# led28.net
KiCad netlist of a schematic drawn in EAGLE
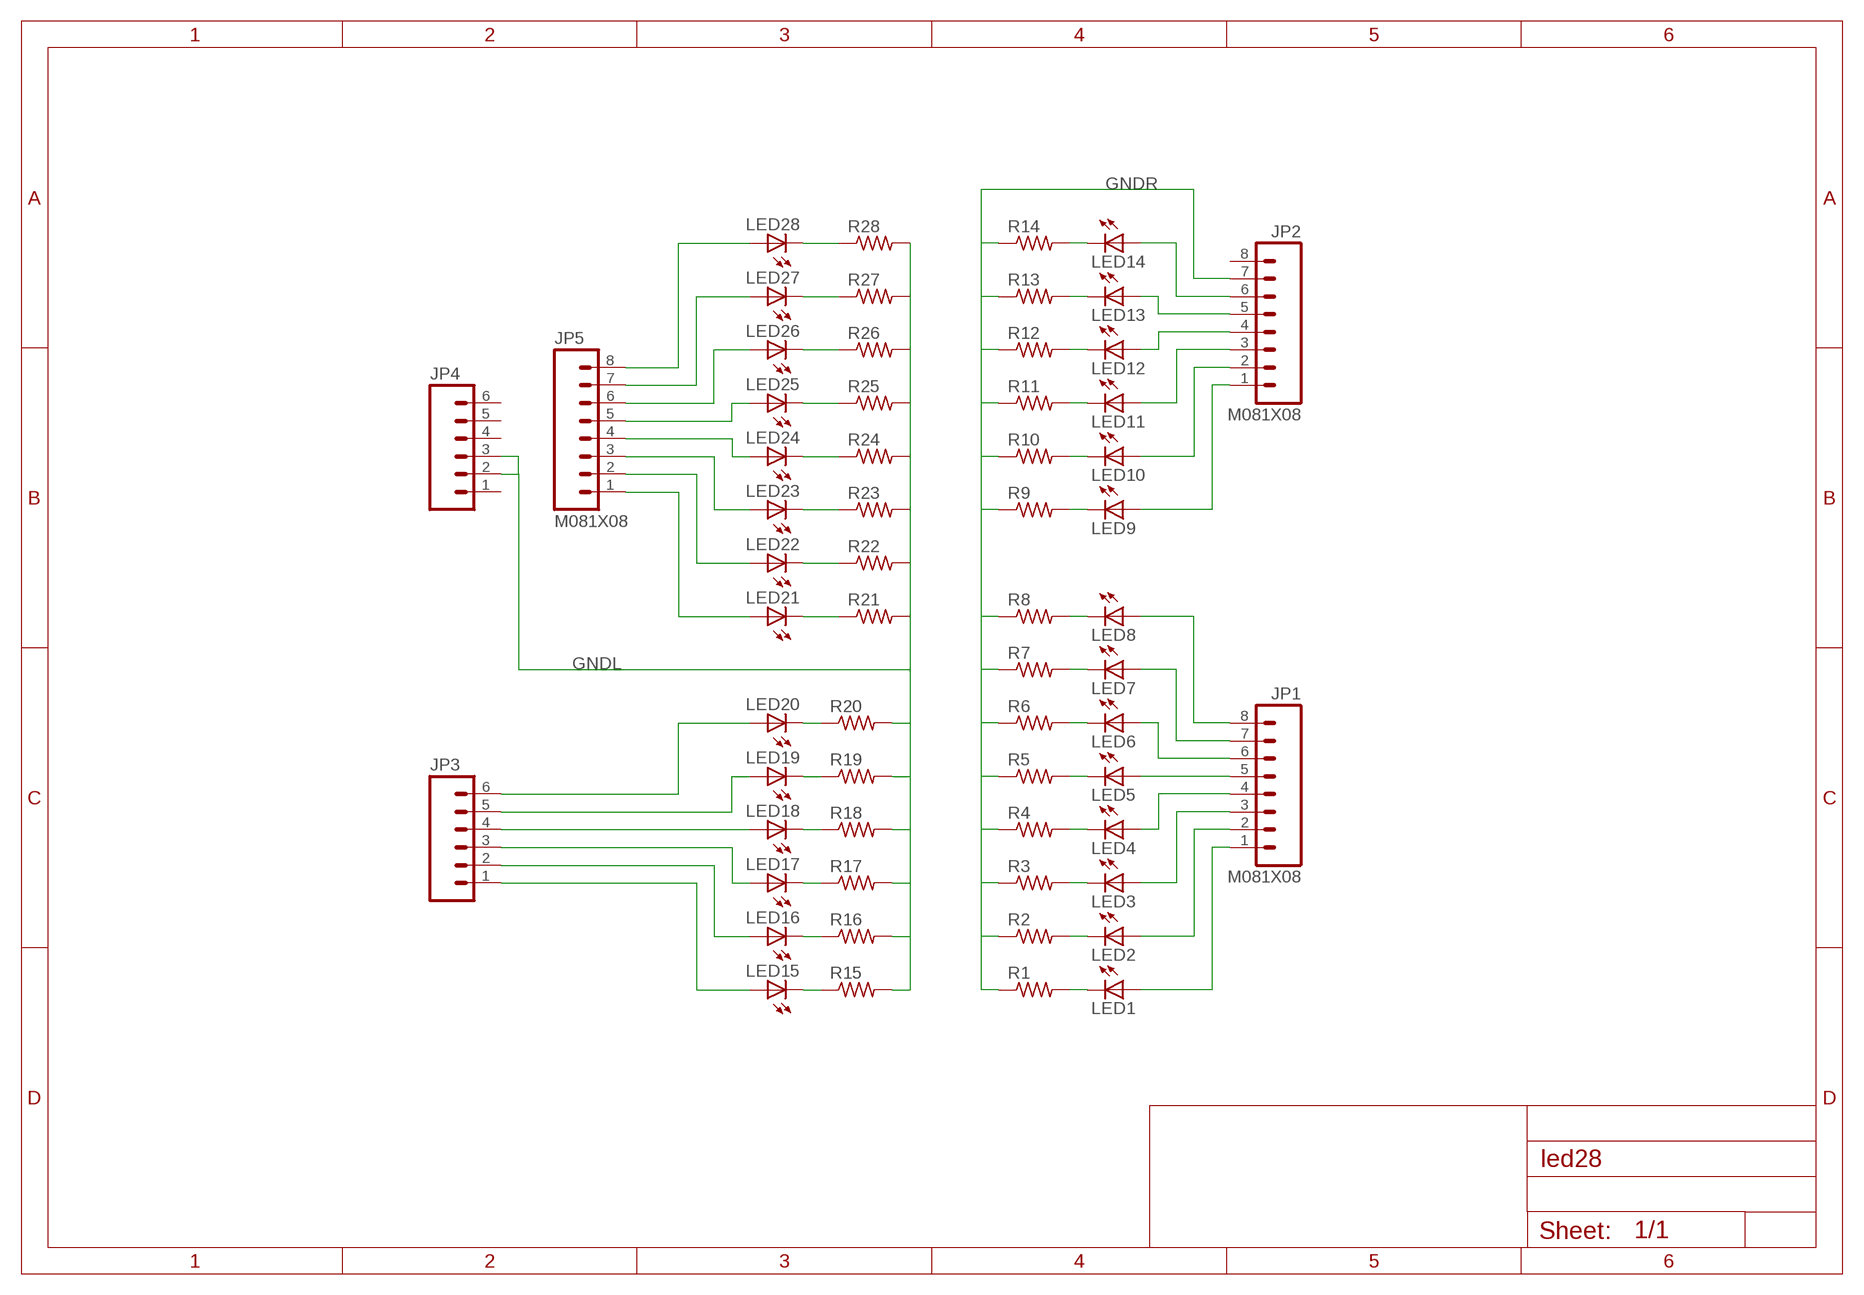
[diagram p0: schematic, sheet 1]

(export (version "E")
  (design (tool "Eeschema 10.0.6"))
  (components
    (comp (ref "JP1")
      (value "M081X08")
      (footprint "eagle-import:1X08_NARROW")
      (libsource (lib "eagle-import") (part "M081X08"))
    )
    (comp (ref "JP2")
      (value "M081X08")
      (footprint "eagle-import:1X08_NARROW")
      (libsource (lib "eagle-import") (part "M081X08"))
    )
    (comp (ref "JP3")
      (value "M06SIP")
      (footprint "eagle-import:1X06_NARROW")
      (libsource (lib "eagle-import") (part "M06SIP"))
    )
    (comp (ref "JP4")
      (value "M06SIP")
      (footprint "eagle-import:1X06_NARROW")
      (libsource (lib "eagle-import") (part "M06SIP"))
    )
    (comp (ref "JP5")
      (value "M081X08")
      (footprint "eagle-import:1X08_NARROW")
      (libsource (lib "eagle-import") (part "M081X08"))
    )
    (comp (ref "LED1")
      (value "LEDCHIP-LED0603")
      (footprint "eagle-import:CHIP-LED0603")
      (libsource (lib "eagle-import") (part "LEDCHIP-LED0603"))
    )
    (comp (ref "LED2")
      (value "LEDCHIP-LED0603")
      (footprint "eagle-import:CHIP-LED0603")
      (libsource (lib "eagle-import") (part "LEDCHIP-LED0603"))
    )
    (comp (ref "LED3")
      (value "LEDCHIP-LED0603")
      (footprint "eagle-import:CHIP-LED0603")
      (libsource (lib "eagle-import") (part "LEDCHIP-LED0603"))
    )
    (comp (ref "LED4")
      (value "LEDCHIP-LED0603")
      (footprint "eagle-import:CHIP-LED0603")
      (libsource (lib "eagle-import") (part "LEDCHIP-LED0603"))
    )
    (comp (ref "LED5")
      (value "LEDCHIP-LED0603")
      (footprint "eagle-import:CHIP-LED0603")
      (libsource (lib "eagle-import") (part "LEDCHIP-LED0603"))
    )
    (comp (ref "LED6")
      (value "LEDCHIP-LED0603")
      (footprint "eagle-import:CHIP-LED0603")
      (libsource (lib "eagle-import") (part "LEDCHIP-LED0603"))
    )
    (comp (ref "LED7")
      (value "LEDCHIP-LED0603")
      (footprint "eagle-import:CHIP-LED0603")
      (libsource (lib "eagle-import") (part "LEDCHIP-LED0603"))
    )
    (comp (ref "LED8")
      (value "LEDCHIP-LED0603")
      (footprint "eagle-import:CHIP-LED0603")
      (libsource (lib "eagle-import") (part "LEDCHIP-LED0603"))
    )
    (comp (ref "LED9")
      (value "LEDCHIP-LED0603")
      (footprint "eagle-import:CHIP-LED0603")
      (libsource (lib "eagle-import") (part "LEDCHIP-LED0603"))
    )
    (comp (ref "LED10")
      (value "LEDCHIP-LED0603")
      (footprint "eagle-import:CHIP-LED0603")
      (libsource (lib "eagle-import") (part "LEDCHIP-LED0603"))
    )
    (comp (ref "LED11")
      (value "LEDCHIP-LED0603")
      (footprint "eagle-import:CHIP-LED0603")
      (libsource (lib "eagle-import") (part "LEDCHIP-LED0603"))
    )
    (comp (ref "LED12")
      (value "LEDCHIP-LED0603")
      (footprint "eagle-import:CHIP-LED0603")
      (libsource (lib "eagle-import") (part "LEDCHIP-LED0603"))
    )
    (comp (ref "LED13")
      (value "LEDCHIP-LED0603")
      (footprint "eagle-import:CHIP-LED0603")
      (libsource (lib "eagle-import") (part "LEDCHIP-LED0603"))
    )
    (comp (ref "LED14")
      (value "LEDCHIP-LED0603")
      (footprint "eagle-import:CHIP-LED0603")
      (libsource (lib "eagle-import") (part "LEDCHIP-LED0603"))
    )
    (comp (ref "LED15")
      (value "LEDCHIP-LED0603")
      (footprint "eagle-import:CHIP-LED0603")
      (libsource (lib "eagle-import") (part "LEDCHIP-LED0603"))
    )
    (comp (ref "LED16")
      (value "LEDCHIP-LED0603")
      (footprint "eagle-import:CHIP-LED0603")
      (libsource (lib "eagle-import") (part "LEDCHIP-LED0603"))
    )
    (comp (ref "LED17")
      (value "LEDCHIP-LED0603")
      (footprint "eagle-import:CHIP-LED0603")
      (libsource (lib "eagle-import") (part "LEDCHIP-LED0603"))
    )
    (comp (ref "LED18")
      (value "LEDCHIP-LED0603")
      (footprint "eagle-import:CHIP-LED0603")
      (libsource (lib "eagle-import") (part "LEDCHIP-LED0603"))
    )
    (comp (ref "LED19")
      (value "LEDCHIP-LED0603")
      (footprint "eagle-import:CHIP-LED0603")
      (libsource (lib "eagle-import") (part "LEDCHIP-LED0603"))
    )
    (comp (ref "LED20")
      (value "LEDCHIP-LED0603")
      (footprint "eagle-import:CHIP-LED0603")
      (libsource (lib "eagle-import") (part "LEDCHIP-LED0603"))
    )
    (comp (ref "LED21")
      (value "LEDCHIP-LED0603")
      (footprint "eagle-import:CHIP-LED0603")
      (libsource (lib "eagle-import") (part "LEDCHIP-LED0603"))
    )
    (comp (ref "LED22")
      (value "LEDCHIP-LED0603")
      (footprint "eagle-import:CHIP-LED0603")
      (libsource (lib "eagle-import") (part "LEDCHIP-LED0603"))
    )
    (comp (ref "LED23")
      (value "LEDCHIP-LED0603")
      (footprint "eagle-import:CHIP-LED0603")
      (libsource (lib "eagle-import") (part "LEDCHIP-LED0603"))
    )
    (comp (ref "LED24")
      (value "LEDCHIP-LED0603")
      (footprint "eagle-import:CHIP-LED0603")
      (libsource (lib "eagle-import") (part "LEDCHIP-LED0603"))
    )
    (comp (ref "LED25")
      (value "LEDCHIP-LED0603")
      (footprint "eagle-import:CHIP-LED0603")
      (libsource (lib "eagle-import") (part "LEDCHIP-LED0603"))
    )
    (comp (ref "LED26")
      (value "LEDCHIP-LED0603")
      (footprint "eagle-import:CHIP-LED0603")
      (libsource (lib "eagle-import") (part "LEDCHIP-LED0603"))
    )
    (comp (ref "LED27")
      (value "LEDCHIP-LED0603")
      (footprint "eagle-import:CHIP-LED0603")
      (libsource (lib "eagle-import") (part "LEDCHIP-LED0603"))
    )
    (comp (ref "LED28")
      (value "LEDCHIP-LED0603")
      (footprint "eagle-import:CHIP-LED0603")
      (libsource (lib "eagle-import") (part "LEDCHIP-LED0603"))
    )
    (comp (ref "R1")
      (value "R-US_R0603")
      (footprint "eagle-import:R0603")
      (libsource (lib "eagle-import") (part "R-US_R0603"))
    )
    (comp (ref "R2")
      (value "R-US_R0603")
      (footprint "eagle-import:R0603")
      (libsource (lib "eagle-import") (part "R-US_R0603"))
    )
    (comp (ref "R3")
      (value "R-US_R0603")
      (footprint "eagle-import:R0603")
      (libsource (lib "eagle-import") (part "R-US_R0603"))
    )
    (comp (ref "R4")
      (value "R-US_R0603")
      (footprint "eagle-import:R0603")
      (libsource (lib "eagle-import") (part "R-US_R0603"))
    )
    (comp (ref "R5")
      (value "R-US_R0603")
      (footprint "eagle-import:R0603")
      (libsource (lib "eagle-import") (part "R-US_R0603"))
    )
    (comp (ref "R6")
      (value "R-US_R0603")
      (footprint "eagle-import:R0603")
      (libsource (lib "eagle-import") (part "R-US_R0603"))
    )
    (comp (ref "R7")
      (value "R-US_R0603")
      (footprint "eagle-import:R0603")
      (libsource (lib "eagle-import") (part "R-US_R0603"))
    )
    (comp (ref "R8")
      (value "R-US_R0603")
      (footprint "eagle-import:R0603")
      (libsource (lib "eagle-import") (part "R-US_R0603"))
    )
    (comp (ref "R9")
      (value "R-US_R0603")
      (footprint "eagle-import:R0603")
      (libsource (lib "eagle-import") (part "R-US_R0603"))
    )
    (comp (ref "R10")
      (value "R-US_R0603")
      (footprint "eagle-import:R0603")
      (libsource (lib "eagle-import") (part "R-US_R0603"))
    )
    (comp (ref "R11")
      (value "R-US_R0603")
      (footprint "eagle-import:R0603")
      (libsource (lib "eagle-import") (part "R-US_R0603"))
    )
    (comp (ref "R12")
      (value "R-US_R0603")
      (footprint "eagle-import:R0603")
      (libsource (lib "eagle-import") (part "R-US_R0603"))
    )
    (comp (ref "R13")
      (value "R-US_R0603")
      (footprint "eagle-import:R0603")
      (libsource (lib "eagle-import") (part "R-US_R0603"))
    )
    (comp (ref "R14")
      (value "R-US_R0603")
      (footprint "eagle-import:R0603")
      (libsource (lib "eagle-import") (part "R-US_R0603"))
    )
    (comp (ref "R15")
      (value "R-US_R0603")
      (footprint "eagle-import:R0603")
      (libsource (lib "eagle-import") (part "R-US_R0603"))
    )
    (comp (ref "R16")
      (value "R-US_R0603")
      (footprint "eagle-import:R0603")
      (libsource (lib "eagle-import") (part "R-US_R0603"))
    )
    (comp (ref "R17")
      (value "R-US_R0603")
      (footprint "eagle-import:R0603")
      (libsource (lib "eagle-import") (part "R-US_R0603"))
    )
    (comp (ref "R18")
      (value "R-US_R0603")
      (footprint "eagle-import:R0603")
      (libsource (lib "eagle-import") (part "R-US_R0603"))
    )
    (comp (ref "R19")
      (value "R-US_R0603")
      (footprint "eagle-import:R0603")
      (libsource (lib "eagle-import") (part "R-US_R0603"))
    )
    (comp (ref "R20")
      (value "R-US_R0603")
      (footprint "eagle-import:R0603")
      (libsource (lib "eagle-import") (part "R-US_R0603"))
    )
    (comp (ref "R21")
      (value "R-US_R0603")
      (footprint "eagle-import:R0603")
      (libsource (lib "eagle-import") (part "R-US_R0603"))
    )
    (comp (ref "R22")
      (value "R-US_R0603")
      (footprint "eagle-import:R0603")
      (libsource (lib "eagle-import") (part "R-US_R0603"))
    )
    (comp (ref "R23")
      (value "R-US_R0603")
      (footprint "eagle-import:R0603")
      (libsource (lib "eagle-import") (part "R-US_R0603"))
    )
    (comp (ref "R24")
      (value "R-US_R0603")
      (footprint "eagle-import:R0603")
      (libsource (lib "eagle-import") (part "R-US_R0603"))
    )
    (comp (ref "R25")
      (value "R-US_R0603")
      (footprint "eagle-import:R0603")
      (libsource (lib "eagle-import") (part "R-US_R0603"))
    )
    (comp (ref "R26")
      (value "R-US_R0603")
      (footprint "eagle-import:R0603")
      (libsource (lib "eagle-import") (part "R-US_R0603"))
    )
    (comp (ref "R27")
      (value "R-US_R0603")
      (footprint "eagle-import:R0603")
      (libsource (lib "eagle-import") (part "R-US_R0603"))
    )
    (comp (ref "R28")
      (value "R-US_R0603")
      (footprint "eagle-import:R0603")
      (libsource (lib "eagle-import") (part "R-US_R0603"))
    )
  )
  (nets
    (net (code "1") (name "/GNDL") (class "Default")
      (node (ref "JP4") (pin "2") (pinfunction "2_2") (pintype "passive"))
      (node (ref "JP4") (pin "3") (pinfunction "3_3") (pintype "passive"))
      (node (ref "R15") (pin "2") (pinfunction "2_2") (pintype "passive"))
      (node (ref "R16") (pin "2") (pinfunction "2_2") (pintype "passive"))
      (node (ref "R17") (pin "2") (pinfunction "2_2") (pintype "passive"))
      (node (ref "R18") (pin "2") (pinfunction "2_2") (pintype "passive"))
      (node (ref "R19") (pin "2") (pinfunction "2_2") (pintype "passive"))
      (node (ref "R20") (pin "2") (pinfunction "2_2") (pintype "passive"))
      (node (ref "R21") (pin "2") (pinfunction "2_2") (pintype "passive"))
      (node (ref "R22") (pin "2") (pinfunction "2_2") (pintype "passive"))
      (node (ref "R23") (pin "2") (pinfunction "2_2") (pintype "passive"))
      (node (ref "R24") (pin "2") (pinfunction "2_2") (pintype "passive"))
      (node (ref "R25") (pin "2") (pinfunction "2_2") (pintype "passive"))
      (node (ref "R26") (pin "2") (pinfunction "2_2") (pintype "passive"))
      (node (ref "R27") (pin "2") (pinfunction "2_2") (pintype "passive"))
      (node (ref "R28") (pin "2") (pinfunction "2_2") (pintype "passive"))
    )
    (net (code "2") (name "/GNDR") (class "Default")
      (node (ref "JP2") (pin "7") (pinfunction "7_7") (pintype "passive"))
      (node (ref "R1") (pin "1") (pinfunction "1_1") (pintype "passive"))
      (node (ref "R10") (pin "1") (pinfunction "1_1") (pintype "passive"))
      (node (ref "R11") (pin "1") (pinfunction "1_1") (pintype "passive"))
      (node (ref "R12") (pin "1") (pinfunction "1_1") (pintype "passive"))
      (node (ref "R13") (pin "1") (pinfunction "1_1") (pintype "passive"))
      (node (ref "R14") (pin "1") (pinfunction "1_1") (pintype "passive"))
      (node (ref "R2") (pin "1") (pinfunction "1_1") (pintype "passive"))
      (node (ref "R3") (pin "1") (pinfunction "1_1") (pintype "passive"))
      (node (ref "R4") (pin "1") (pinfunction "1_1") (pintype "passive"))
      (node (ref "R5") (pin "1") (pinfunction "1_1") (pintype "passive"))
      (node (ref "R6") (pin "1") (pinfunction "1_1") (pintype "passive"))
      (node (ref "R7") (pin "1") (pinfunction "1_1") (pintype "passive"))
      (node (ref "R8") (pin "1") (pinfunction "1_1") (pintype "passive"))
      (node (ref "R9") (pin "1") (pinfunction "1_1") (pintype "passive"))
    )
    (net (code "3") (name "Net-(JP1-Pad1)") (class "Default")
      (node (ref "JP1") (pin "1") (pinfunction "1_1") (pintype "passive"))
      (node (ref "LED1") (pin "A") (pinfunction "A_A") (pintype "passive"))
    )
    (net (code "4") (name "Net-(JP1-Pad2)") (class "Default")
      (node (ref "JP1") (pin "2") (pinfunction "2_2") (pintype "passive"))
      (node (ref "LED2") (pin "A") (pinfunction "A_A") (pintype "passive"))
    )
    (net (code "5") (name "Net-(JP1-Pad3)") (class "Default")
      (node (ref "JP1") (pin "3") (pinfunction "3_3") (pintype "passive"))
      (node (ref "LED3") (pin "A") (pinfunction "A_A") (pintype "passive"))
    )
    (net (code "6") (name "Net-(JP1-Pad4)") (class "Default")
      (node (ref "JP1") (pin "4") (pinfunction "4_4") (pintype "passive"))
      (node (ref "LED4") (pin "A") (pinfunction "A_A") (pintype "passive"))
    )
    (net (code "7") (name "Net-(JP1-Pad5)") (class "Default")
      (node (ref "JP1") (pin "5") (pinfunction "5_5") (pintype "passive"))
      (node (ref "LED5") (pin "A") (pinfunction "A_A") (pintype "passive"))
    )
    (net (code "8") (name "Net-(JP1-Pad6)") (class "Default")
      (node (ref "JP1") (pin "6") (pinfunction "6_6") (pintype "passive"))
      (node (ref "LED6") (pin "A") (pinfunction "A_A") (pintype "passive"))
    )
    (net (code "9") (name "Net-(JP1-Pad7)") (class "Default")
      (node (ref "JP1") (pin "7") (pinfunction "7_7") (pintype "passive"))
      (node (ref "LED7") (pin "A") (pinfunction "A_A") (pintype "passive"))
    )
    (net (code "10") (name "Net-(JP1-Pad8)") (class "Default")
      (node (ref "JP1") (pin "8") (pinfunction "8_8") (pintype "passive"))
      (node (ref "LED8") (pin "A") (pinfunction "A_A") (pintype "passive"))
    )
    (net (code "11") (name "Net-(JP2-Pad1)") (class "Default")
      (node (ref "JP2") (pin "1") (pinfunction "1_1") (pintype "passive"))
      (node (ref "LED9") (pin "A") (pinfunction "A_A") (pintype "passive"))
    )
    (net (code "12") (name "Net-(JP2-Pad2)") (class "Default")
      (node (ref "JP2") (pin "2") (pinfunction "2_2") (pintype "passive"))
      (node (ref "LED10") (pin "A") (pinfunction "A_A") (pintype "passive"))
    )
    (net (code "13") (name "Net-(JP2-Pad3)") (class "Default")
      (node (ref "JP2") (pin "3") (pinfunction "3_3") (pintype "passive"))
      (node (ref "LED11") (pin "A") (pinfunction "A_A") (pintype "passive"))
    )
    (net (code "14") (name "Net-(JP2-Pad4)") (class "Default")
      (node (ref "JP2") (pin "4") (pinfunction "4_4") (pintype "passive"))
      (node (ref "LED12") (pin "A") (pinfunction "A_A") (pintype "passive"))
    )
    (net (code "15") (name "Net-(JP2-Pad5)") (class "Default")
      (node (ref "JP2") (pin "5") (pinfunction "5_5") (pintype "passive"))
      (node (ref "LED13") (pin "A") (pinfunction "A_A") (pintype "passive"))
    )
    (net (code "16") (name "Net-(JP2-Pad6)") (class "Default")
      (node (ref "JP2") (pin "6") (pinfunction "6_6") (pintype "passive"))
      (node (ref "LED14") (pin "A") (pinfunction "A_A") (pintype "passive"))
    )
    (net (code "17") (name "Net-(JP3-Pad1)") (class "Default")
      (node (ref "JP3") (pin "1") (pinfunction "1_1") (pintype "passive"))
      (node (ref "LED15") (pin "A") (pinfunction "A_A") (pintype "passive"))
    )
    (net (code "18") (name "Net-(JP3-Pad2)") (class "Default")
      (node (ref "JP3") (pin "2") (pinfunction "2_2") (pintype "passive"))
      (node (ref "LED16") (pin "A") (pinfunction "A_A") (pintype "passive"))
    )
    (net (code "19") (name "Net-(JP3-Pad3)") (class "Default")
      (node (ref "JP3") (pin "3") (pinfunction "3_3") (pintype "passive"))
      (node (ref "LED17") (pin "A") (pinfunction "A_A") (pintype "passive"))
    )
    (net (code "20") (name "Net-(JP3-Pad4)") (class "Default")
      (node (ref "JP3") (pin "4") (pinfunction "4_4") (pintype "passive"))
      (node (ref "LED18") (pin "A") (pinfunction "A_A") (pintype "passive"))
    )
    (net (code "21") (name "Net-(JP3-Pad5)") (class "Default")
      (node (ref "JP3") (pin "5") (pinfunction "5_5") (pintype "passive"))
      (node (ref "LED19") (pin "A") (pinfunction "A_A") (pintype "passive"))
    )
    (net (code "22") (name "Net-(JP3-Pad6)") (class "Default")
      (node (ref "JP3") (pin "6") (pinfunction "6_6") (pintype "passive"))
      (node (ref "LED20") (pin "A") (pinfunction "A_A") (pintype "passive"))
    )
    (net (code "23") (name "Net-(JP5-Pad1)") (class "Default")
      (node (ref "JP5") (pin "1") (pinfunction "1_1") (pintype "passive"))
      (node (ref "LED21") (pin "A") (pinfunction "A_A") (pintype "passive"))
    )
    (net (code "24") (name "Net-(JP5-Pad2)") (class "Default")
      (node (ref "JP5") (pin "2") (pinfunction "2_2") (pintype "passive"))
      (node (ref "LED22") (pin "A") (pinfunction "A_A") (pintype "passive"))
    )
    (net (code "25") (name "Net-(JP5-Pad3)") (class "Default")
      (node (ref "JP5") (pin "3") (pinfunction "3_3") (pintype "passive"))
      (node (ref "LED23") (pin "A") (pinfunction "A_A") (pintype "passive"))
    )
    (net (code "26") (name "Net-(JP5-Pad4)") (class "Default")
      (node (ref "JP5") (pin "4") (pinfunction "4_4") (pintype "passive"))
      (node (ref "LED24") (pin "A") (pinfunction "A_A") (pintype "passive"))
    )
    (net (code "27") (name "Net-(JP5-Pad5)") (class "Default")
      (node (ref "JP5") (pin "5") (pinfunction "5_5") (pintype "passive"))
      (node (ref "LED25") (pin "A") (pinfunction "A_A") (pintype "passive"))
    )
    (net (code "28") (name "Net-(JP5-Pad6)") (class "Default")
      (node (ref "JP5") (pin "6") (pinfunction "6_6") (pintype "passive"))
      (node (ref "LED26") (pin "A") (pinfunction "A_A") (pintype "passive"))
    )
    (net (code "29") (name "Net-(JP5-Pad7)") (class "Default")
      (node (ref "JP5") (pin "7") (pinfunction "7_7") (pintype "passive"))
      (node (ref "LED27") (pin "A") (pinfunction "A_A") (pintype "passive"))
    )
    (net (code "30") (name "Net-(JP5-Pad8)") (class "Default")
      (node (ref "JP5") (pin "8") (pinfunction "8_8") (pintype "passive"))
      (node (ref "LED28") (pin "A") (pinfunction "A_A") (pintype "passive"))
    )
    (net (code "31") (name "Net-(LED1-PadC)") (class "Default")
      (node (ref "LED1") (pin "C") (pinfunction "C_C") (pintype "passive"))
      (node (ref "R1") (pin "2") (pinfunction "2_2") (pintype "passive"))
    )
    (net (code "32") (name "Net-(LED2-PadC)") (class "Default")
      (node (ref "LED2") (pin "C") (pinfunction "C_C") (pintype "passive"))
      (node (ref "R2") (pin "2") (pinfunction "2_2") (pintype "passive"))
    )
    (net (code "33") (name "Net-(LED3-PadC)") (class "Default")
      (node (ref "LED3") (pin "C") (pinfunction "C_C") (pintype "passive"))
      (node (ref "R3") (pin "2") (pinfunction "2_2") (pintype "passive"))
    )
    (net (code "34") (name "Net-(LED4-PadC)") (class "Default")
      (node (ref "LED4") (pin "C") (pinfunction "C_C") (pintype "passive"))
      (node (ref "R4") (pin "2") (pinfunction "2_2") (pintype "passive"))
    )
    (net (code "35") (name "Net-(LED5-PadC)") (class "Default")
      (node (ref "LED5") (pin "C") (pinfunction "C_C") (pintype "passive"))
      (node (ref "R5") (pin "2") (pinfunction "2_2") (pintype "passive"))
    )
    (net (code "36") (name "Net-(LED6-PadC)") (class "Default")
      (node (ref "LED6") (pin "C") (pinfunction "C_C") (pintype "passive"))
      (node (ref "R6") (pin "2") (pinfunction "2_2") (pintype "passive"))
    )
    (net (code "37") (name "Net-(LED7-PadC)") (class "Default")
      (node (ref "LED7") (pin "C") (pinfunction "C_C") (pintype "passive"))
      (node (ref "R7") (pin "2") (pinfunction "2_2") (pintype "passive"))
    )
    (net (code "38") (name "Net-(LED8-PadC)") (class "Default")
      (node (ref "LED8") (pin "C") (pinfunction "C_C") (pintype "passive"))
      (node (ref "R8") (pin "2") (pinfunction "2_2") (pintype "passive"))
    )
    (net (code "39") (name "Net-(LED9-PadC)") (class "Default")
      (node (ref "LED9") (pin "C") (pinfunction "C_C") (pintype "passive"))
      (node (ref "R9") (pin "2") (pinfunction "2_2") (pintype "passive"))
    )
    (net (code "40") (name "Net-(LED10-PadC)") (class "Default")
      (node (ref "LED10") (pin "C") (pinfunction "C_C") (pintype "passive"))
      (node (ref "R10") (pin "2") (pinfunction "2_2") (pintype "passive"))
    )
    (net (code "41") (name "Net-(LED11-PadC)") (class "Default")
      (node (ref "LED11") (pin "C") (pinfunction "C_C") (pintype "passive"))
      (node (ref "R11") (pin "2") (pinfunction "2_2") (pintype "passive"))
    )
    (net (code "42") (name "Net-(LED12-PadC)") (class "Default")
      (node (ref "LED12") (pin "C") (pinfunction "C_C") (pintype "passive"))
      (node (ref "R12") (pin "2") (pinfunction "2_2") (pintype "passive"))
    )
    (net (code "43") (name "Net-(LED13-PadC)") (class "Default")
      (node (ref "LED13") (pin "C") (pinfunction "C_C") (pintype "passive"))
      (node (ref "R13") (pin "2") (pinfunction "2_2") (pintype "passive"))
    )
    (net (code "44") (name "Net-(LED14-PadC)") (class "Default")
      (node (ref "LED14") (pin "C") (pinfunction "C_C") (pintype "passive"))
      (node (ref "R14") (pin "2") (pinfunction "2_2") (pintype "passive"))
    )
    (net (code "45") (name "Net-(LED15-PadC)") (class "Default")
      (node (ref "LED15") (pin "C") (pinfunction "C_C") (pintype "passive"))
      (node (ref "R15") (pin "1") (pinfunction "1_1") (pintype "passive"))
    )
    (net (code "46") (name "Net-(LED16-PadC)") (class "Default")
      (node (ref "LED16") (pin "C") (pinfunction "C_C") (pintype "passive"))
      (node (ref "R16") (pin "1") (pinfunction "1_1") (pintype "passive"))
    )
    (net (code "47") (name "Net-(LED17-PadC)") (class "Default")
      (node (ref "LED17") (pin "C") (pinfunction "C_C") (pintype "passive"))
      (node (ref "R17") (pin "1") (pinfunction "1_1") (pintype "passive"))
    )
    (net (code "48") (name "Net-(LED18-PadC)") (class "Default")
      (node (ref "LED18") (pin "C") (pinfunction "C_C") (pintype "passive"))
      (node (ref "R18") (pin "1") (pinfunction "1_1") (pintype "passive"))
    )
    (net (code "49") (name "Net-(LED19-PadC)") (class "Default")
      (node (ref "LED19") (pin "C") (pinfunction "C_C") (pintype "passive"))
      (node (ref "R19") (pin "1") (pinfunction "1_1") (pintype "passive"))
    )
    (net (code "50") (name "Net-(LED20-PadC)") (class "Default")
      (node (ref "LED20") (pin "C") (pinfunction "C_C") (pintype "passive"))
      (node (ref "R20") (pin "1") (pinfunction "1_1") (pintype "passive"))
    )
    (net (code "51") (name "Net-(LED21-PadC)") (class "Default")
      (node (ref "LED21") (pin "C") (pinfunction "C_C") (pintype "passive"))
      (node (ref "R21") (pin "1") (pinfunction "1_1") (pintype "passive"))
    )
    (net (code "52") (name "Net-(LED22-PadC)") (class "Default")
      (node (ref "LED22") (pin "C") (pinfunction "C_C") (pintype "passive"))
      (node (ref "R22") (pin "1") (pinfunction "1_1") (pintype "passive"))
    )
    (net (code "53") (name "Net-(LED23-PadC)") (class "Default")
      (node (ref "LED23") (pin "C") (pinfunction "C_C") (pintype "passive"))
      (node (ref "R23") (pin "1") (pinfunction "1_1") (pintype "passive"))
    )
    (net (code "54") (name "Net-(LED24-PadC)") (class "Default")
      (node (ref "LED24") (pin "C") (pinfunction "C_C") (pintype "passive"))
      (node (ref "R24") (pin "1") (pinfunction "1_1") (pintype "passive"))
    )
    (net (code "55") (name "Net-(LED25-PadC)") (class "Default")
      (node (ref "LED25") (pin "C") (pinfunction "C_C") (pintype "passive"))
      (node (ref "R25") (pin "1") (pinfunction "1_1") (pintype "passive"))
    )
    (net (code "56") (name "Net-(LED26-PadC)") (class "Default")
      (node (ref "LED26") (pin "C") (pinfunction "C_C") (pintype "passive"))
      (node (ref "R26") (pin "1") (pinfunction "1_1") (pintype "passive"))
    )
    (net (code "57") (name "Net-(LED27-PadC)") (class "Default")
      (node (ref "LED27") (pin "C") (pinfunction "C_C") (pintype "passive"))
      (node (ref "R27") (pin "1") (pinfunction "1_1") (pintype "passive"))
    )
    (net (code "58") (name "Net-(LED28-PadC)") (class "Default")
      (node (ref "LED28") (pin "C") (pinfunction "C_C") (pintype "passive"))
      (node (ref "R28") (pin "1") (pinfunction "1_1") (pintype "passive"))
    )
    (net (code "59") (name "unconnected-(JP2-Pad8)") (class "Default")
      (node (ref "JP2") (pin "8") (pinfunction "8_8") (pintype "passive"))
    )
    (net (code "60") (name "unconnected-(JP4-Pad1)") (class "Default")
      (node (ref "JP4") (pin "1") (pinfunction "1_1") (pintype "passive"))
    )
    (net (code "61") (name "unconnected-(JP4-Pad4)") (class "Default")
      (node (ref "JP4") (pin "4") (pinfunction "4_4") (pintype "passive"))
    )
    (net (code "62") (name "unconnected-(JP4-Pad5)") (class "Default")
      (node (ref "JP4") (pin "5") (pinfunction "5_5") (pintype "passive"))
    )
    (net (code "63") (name "unconnected-(JP4-Pad6)") (class "Default")
      (node (ref "JP4") (pin "6") (pinfunction "6_6") (pintype "passive"))
    )
  )
)
